# STATUS_RGB.net
KiCad netlist of a schematic drawn in Altium Designer
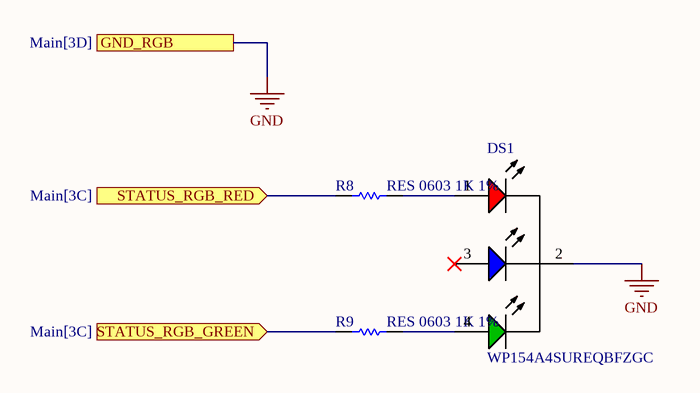
[diagram p0: STATUS_RGB.SchDoc]

(export (version "E")
  (design (tool "Eeschema 10.0.6"))
  (components
    (comp (ref "DS1")
      (value "WP154A4SUREQBFZGC")
      (footprint "KING-WP154A4SUREQBFZGC_V")
      (description "Full Color LED Lamp, Dominant Wavelength RGB 630 / 525 / 465 nm, -40 to 85 degC, 4-Pin THD, RoHS")
      (fields (field (name "MANUFACTURER") "Kingbright"))
      (libsource (lib "Altium Content Vault") (part "LED-RGB-AKAA-4"))
    )
    (comp (ref "R8")
      (value "RES 0603 1K 1%")
      (footprint "0603_RES")
      (description "Resistor Surface Mount, 1K Ohms, 0603 Footprint, 1% Tolerance 0.1W")
      (fields (field (name "MANUFACTURER") "Various") (field (name "TOLERANCE") "1%"))
      (libsource (lib "University of Pennsylvania (ESE)") (part "res"))
    )
    (comp (ref "R9")
      (value "RES 0603 1K 1%")
      (footprint "0603_RES")
      (description "Resistor Surface Mount, 1K Ohms, 0603 Footprint, 1% Tolerance 0.1W")
      (fields (field (name "MANUFACTURER") "Various") (field (name "TOLERANCE") "1%"))
      (libsource (lib "University of Pennsylvania (ESE)") (part "res"))
    )
  )
  (nets
    (net (code "1") (name "/STATUS_RGB_GREEN") (class "Default")
      (node (ref "R9") (pin "2") (pinfunction "2_2") (pintype "passive"))
    )
    (net (code "2") (name "/STATUS_RGB_RED") (class "Default")
      (node (ref "R8") (pin "2") (pinfunction "2_2") (pintype "passive"))
    )
    (net (code "3") (name "GND") (class "Default")
      (node (ref "DS1") (pin "2") (pinfunction "CATHODE_2") (pintype "passive"))
    )
    (net (code "4") (name "Net-(DS1-GREEN)") (class "Default")
      (node (ref "DS1") (pin "4") (pinfunction "GREEN_4") (pintype "passive"))
      (node (ref "R9") (pin "1") (pinfunction "1_1") (pintype "passive"))
    )
    (net (code "5") (name "Net-(DS1-RED)") (class "Default")
      (node (ref "DS1") (pin "1") (pinfunction "RED_1") (pintype "passive"))
      (node (ref "R8") (pin "1") (pinfunction "1_1") (pintype "passive"))
    )
    (net (code "6") (name "unconnected-(DS1-BLUE-Pad3)") (class "Default")
      (node (ref "DS1") (pin "3") (pinfunction "BLUE_3") (pintype "passive+no_connect"))
    )
  )
)
